# Steering_Wheel_Interface_Analog_Inputs.net
KiCad netlist of a schematic drawn in Altium Designer
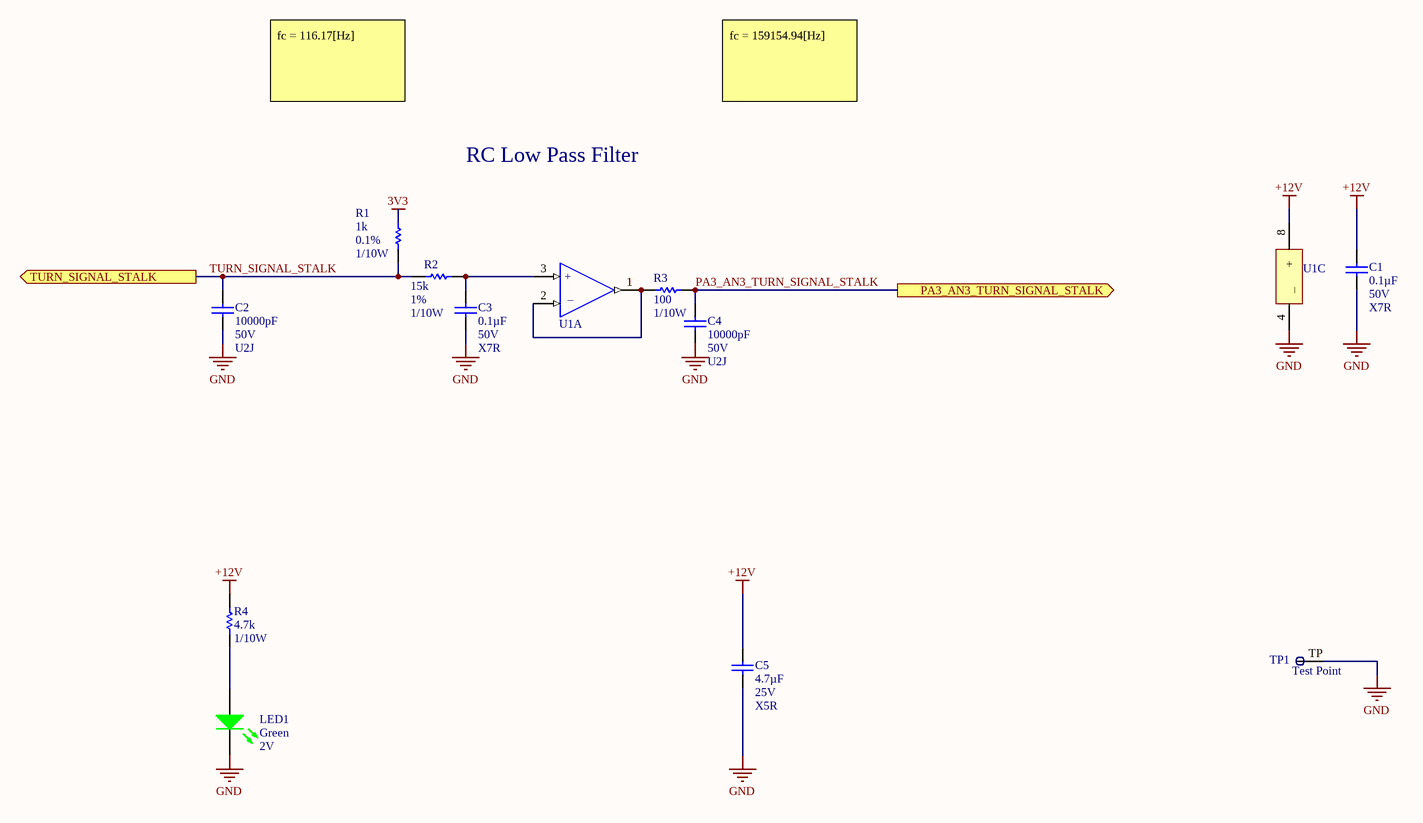
[diagram p0: Steering Wheel Interface Analog Inputs.SchDoc]

(export (version "E")
  (design (tool "Eeschema 10.0.6"))
  (components
    (comp (ref "C1")
      (value "CAP CER 0.1UF 50V 10% X7R 0603")
      (footprint "CAP, 0603")
      (description "0.10µF ±10% 50V Ceramic Capacitor X7R 0603 (1608 Metric)")
      (fields
        (field (name "TOLERANCE") "±10%")
        (field (name "CAPACITANCE") "0.1µF")
        (field (name "VOLTAGE") "50V")
        (field (name "TEMPERATURE COEFFICIENT") "X7R")
      )
      (libsource (lib "Schematic Diagrams") (part "CAP CER 0.1UF 50V 10% X7R 0603"))
    )
    (comp (ref "C2")
      (value "CAP CER 10nF 50V 5% X7R 0603")
      (footprint "CAP, 0603")
      (description "10000pF ±5% 50V Ceramic Capacitor U2J 0603 (1608 Metric)")
      (fields
        (field (name "TOLERANCE") "±5%")
        (field (name "CAPACITANCE") "10000pF")
        (field (name "VOLTAGE") "50V")
        (field (name "TEMPERATURE COEFFICIENT") "U2J")
      )
      (libsource (lib "Schematic Diagrams") (part "CAP CER 10nF 50V 5% X7R 0603"))
    )
    (comp (ref "C3")
      (value "CAP CER 0.1UF 50V 10% X7R 0603")
      (footprint "CAP, 0603")
      (description "0.10µF ±10% 50V Ceramic Capacitor X7R 0603 (1608 Metric)")
      (fields
        (field (name "TOLERANCE") "±10%")
        (field (name "CAPACITANCE") "0.1µF")
        (field (name "VOLTAGE") "50V")
        (field (name "TEMPERATURE COEFFICIENT") "X7R")
      )
      (libsource (lib "Schematic Diagrams") (part "CAP CER 0.1UF 50V 10% X7R 0603"))
    )
    (comp (ref "C4")
      (value "CAP CER 10nF 50V 5% X7R 0603")
      (footprint "CAP, 0603")
      (description "10000pF ±5% 50V Ceramic Capacitor U2J 0603 (1608 Metric)")
      (fields
        (field (name "TOLERANCE") "±5%")
        (field (name "CAPACITANCE") "10000pF")
        (field (name "VOLTAGE") "50V")
        (field (name "TEMPERATURE COEFFICIENT") "U2J")
      )
      (libsource (lib "Schematic Diagrams") (part "CAP CER 10nF 50V 5% X7R 0603"))
    )
    (comp (ref "C5")
      (value "CAP CER 4.7UF 25V 10% X5R 0603")
      (footprint "CAP, 0603")
      (description "4.7µF ±10% 25V Ceramic Capacitor X5R 0603 (1608 Metric)")
      (fields
        (field (name "TOLERANCE") "±10%")
        (field (name "CAPACITANCE") "4.7µF")
        (field (name "VOLTAGE") "25V")
        (field (name "TEMPERATURE COEFFICIENT") "X5R")
      )
      (libsource (lib "Schematic Diagrams") (part "CAP CER 4.7UF 25V 10% X5R 0603"))
    )
    (comp (ref "LED1")
      (value "LED GREEN CLEAR 2V 0603")
      (footprint "LED_0603")
      (description "Green 572nm LED Indication - Discrete 2V 0603 (1608 Metric)")
      (fields
        (field (name "MANUFACTURER") "Wurth Electronics Inc.")
        (field (name "MANUFACTURER PART NUMBER") "150060VS75000")
        (field (name "COLOR") "Green")
        (field (name "VOLTAGE - FORWARD (VF) (TYP)") "2V")
      )
      (libsource (lib "Schematic Diagrams") (part "LED GREEN CLEAR 2V 0603"))
    )
    (comp (ref "R1")
      (value "RES SMD 1K OHM 0.1% 1/10W 0603")
      (footprint "RES, 0603")
      (description "1 kOhms ±0.1% 0.1W, 1/10W Chip Resistor 0603 (1608 Metric) Automotive AEC-Q200 Thin Film")
      (fields
        (field (name "MANUFACTURER") "Panasonic")
        (field (name "MANUFACTURER PART NUMBER") "ERA3AEB102V")
        (field (name "RESISTANCE") "1k")
        (field (name "TOLERANCE") "0.1%")
        (field (name "POWER RATING") "1/10W")
      )
      (libsource (lib "Schematic Diagrams") (part "RES SMD 1K OHM 0.1% 1/10W 0603"))
    )
    (comp (ref "R2")
      (value "RES SMD 15K OHM 1% 1/10W 0603")
      (footprint "RES, 0603")
      (description "15 kOhms ±1% 0.1W, 1/10W Chip Resistor 0603 (1608 Metric) Moisture Resistant Thick Film")
      (fields
        (field (name "RESISTANCE") "15k")
        (field (name "TOLERANCE") "1%")
        (field (name "MAX POWER DISSIPATION") "1/10W")
        (field (name "MANUFACTURER") "Yageo")
        (field (name "MANUFACTURER PART NUMBER") "RC0603FR-0715KL")
      )
      (libsource (lib "Schematic Diagrams") (part "RES SMD 15K OHM 1% 1/10W 0603"))
    )
    (comp (ref "R3")
      (value "RES 100 OHM 1% 1/10W 0603")
      (footprint "RES, 0603")
      (description "100 Ohm ±1% 0.1W, 1/10W Chip Resistor 0603 (1608 Metric) Moisture Resistant Thick Film")
      (fields
        (field (name "TOLERANCE") "±1%")
        (field (name "RESISTANCE") "100")
        (field (name "POWER") "1/10W")
      )
      (libsource (lib "Schematic Diagrams") (part "RES 100 OHM 1% 1/10W 0603"))
    )
    (comp (ref "R4")
      (value "RES 4.7K OHM 1% 1/10W 0603")
      (footprint "RES, 0603")
      (description "4.7k Ohm ±1% 0.1W, 1/10W Chip Resistor 0603 (1608 Metric) Moisture Resistant Thick Film")
      (fields
        (field (name "TOLERANCE") "±1%")
        (field (name "RESISTANCE (OHMS)") "4.7k")
        (field (name "POWER (WATTS)") "1/10W")
      )
      (libsource (lib "Schematic Diagrams") (part "RES 4.7K OHM 1% 1/10W 0603"))
    )
    (comp (ref "TP1")
      (value "Test Point")
      (footprint "Test Point")
      (libsource (lib "Schematic Diagrams") (part "Test Point"))
    )
    (comp (ref "U1")
      (value "IC OP AMP DUAL GP RR 10MHZ 8-VSSOP")
      (footprint "IC OP AMP DUAL 8-VSSOP")
      (description "General Purpose Amplifier 2 Circuit Rail-to-Rail 8-VSSOP")
      (fields
        (field (name "MANUFACTURER") "Texas Instruments")
        (field (name "MANUFACTURER PART NUMBER") "OPA2197IDGKR")
      )
      (libsource (lib "Schematic Diagrams") (part "IC OP AMP DUAL GP RR 10MHZ 8-VSSOP"))
    )
  )
  (nets
    (net (code "1") (name "+12V") (class "Default")
      (node (ref "C1") (pin "1") (pinfunction "1_1") (pintype "passive"))
      (node (ref "C5") (pin "1") (pinfunction "1_1") (pintype "passive"))
      (node (ref "R4") (pin "1") (pinfunction "1_1") (pintype "passive"))
      (node (ref "U1") (pin "8") (pinfunction "+_8") (pintype "power_in"))
    )
    (net (code "2") (name "/PA3_AN3_TURN_SIGNAL_STALK") (class "Default")
      (node (ref "C4") (pin "1") (pinfunction "1_1") (pintype "passive"))
      (node (ref "R3") (pin "1") (pinfunction "1_1") (pintype "passive"))
    )
    (net (code "3") (name "/TURN_SIGNAL_STALK") (class "Default")
      (node (ref "C2") (pin "1") (pinfunction "1_1") (pintype "passive"))
      (node (ref "R1") (pin "2") (pinfunction "2_2") (pintype "passive"))
      (node (ref "R2") (pin "2") (pinfunction "2_2") (pintype "passive"))
    )
    (net (code "4") (name "3V3") (class "Default")
      (node (ref "R1") (pin "1") (pinfunction "1_1") (pintype "passive"))
    )
    (net (code "5") (name "GND") (class "Default")
      (node (ref "C1") (pin "2") (pinfunction "2_2") (pintype "passive"))
      (node (ref "C2") (pin "2") (pinfunction "2_2") (pintype "passive"))
      (node (ref "C3") (pin "2") (pinfunction "2_2") (pintype "passive"))
      (node (ref "C4") (pin "2") (pinfunction "2_2") (pintype "passive"))
      (node (ref "C5") (pin "2") (pinfunction "2_2") (pintype "passive"))
      (node (ref "LED1") (pin "2") (pinfunction "K_2") (pintype "passive"))
      (node (ref "TP1") (pin "TP") (pinfunction "1_TP") (pintype "passive"))
      (node (ref "U1") (pin "4") (pinfunction "__4") (pintype "power_in"))
    )
    (net (code "6") (name "Net-(LED1-A)") (class "Default")
      (node (ref "LED1") (pin "1") (pinfunction "A_1") (pintype "passive"))
      (node (ref "R4") (pin "2") (pinfunction "2_2") (pintype "passive"))
    )
    (net (code "7") (name "Net-(U1A-+IN_A)") (class "Default")
      (node (ref "C3") (pin "1") (pinfunction "1_1") (pintype "passive"))
      (node (ref "R2") (pin "1") (pinfunction "1_1") (pintype "passive"))
      (node (ref "U1") (pin "3") (pinfunction "+IN_A_3") (pintype "input"))
    )
    (net (code "8") (name "Net-(U1A--IN_A)") (class "Default")
      (node (ref "R3") (pin "2") (pinfunction "2_2") (pintype "passive"))
      (node (ref "U1") (pin "1") (pinfunction "OUT_A_1") (pintype "output"))
      (node (ref "U1") (pin "2") (pinfunction "-IN_A_2") (pintype "input"))
    )
  )
)
